# sensorboard.net
KiCad netlist of a schematic drawn in EAGLE
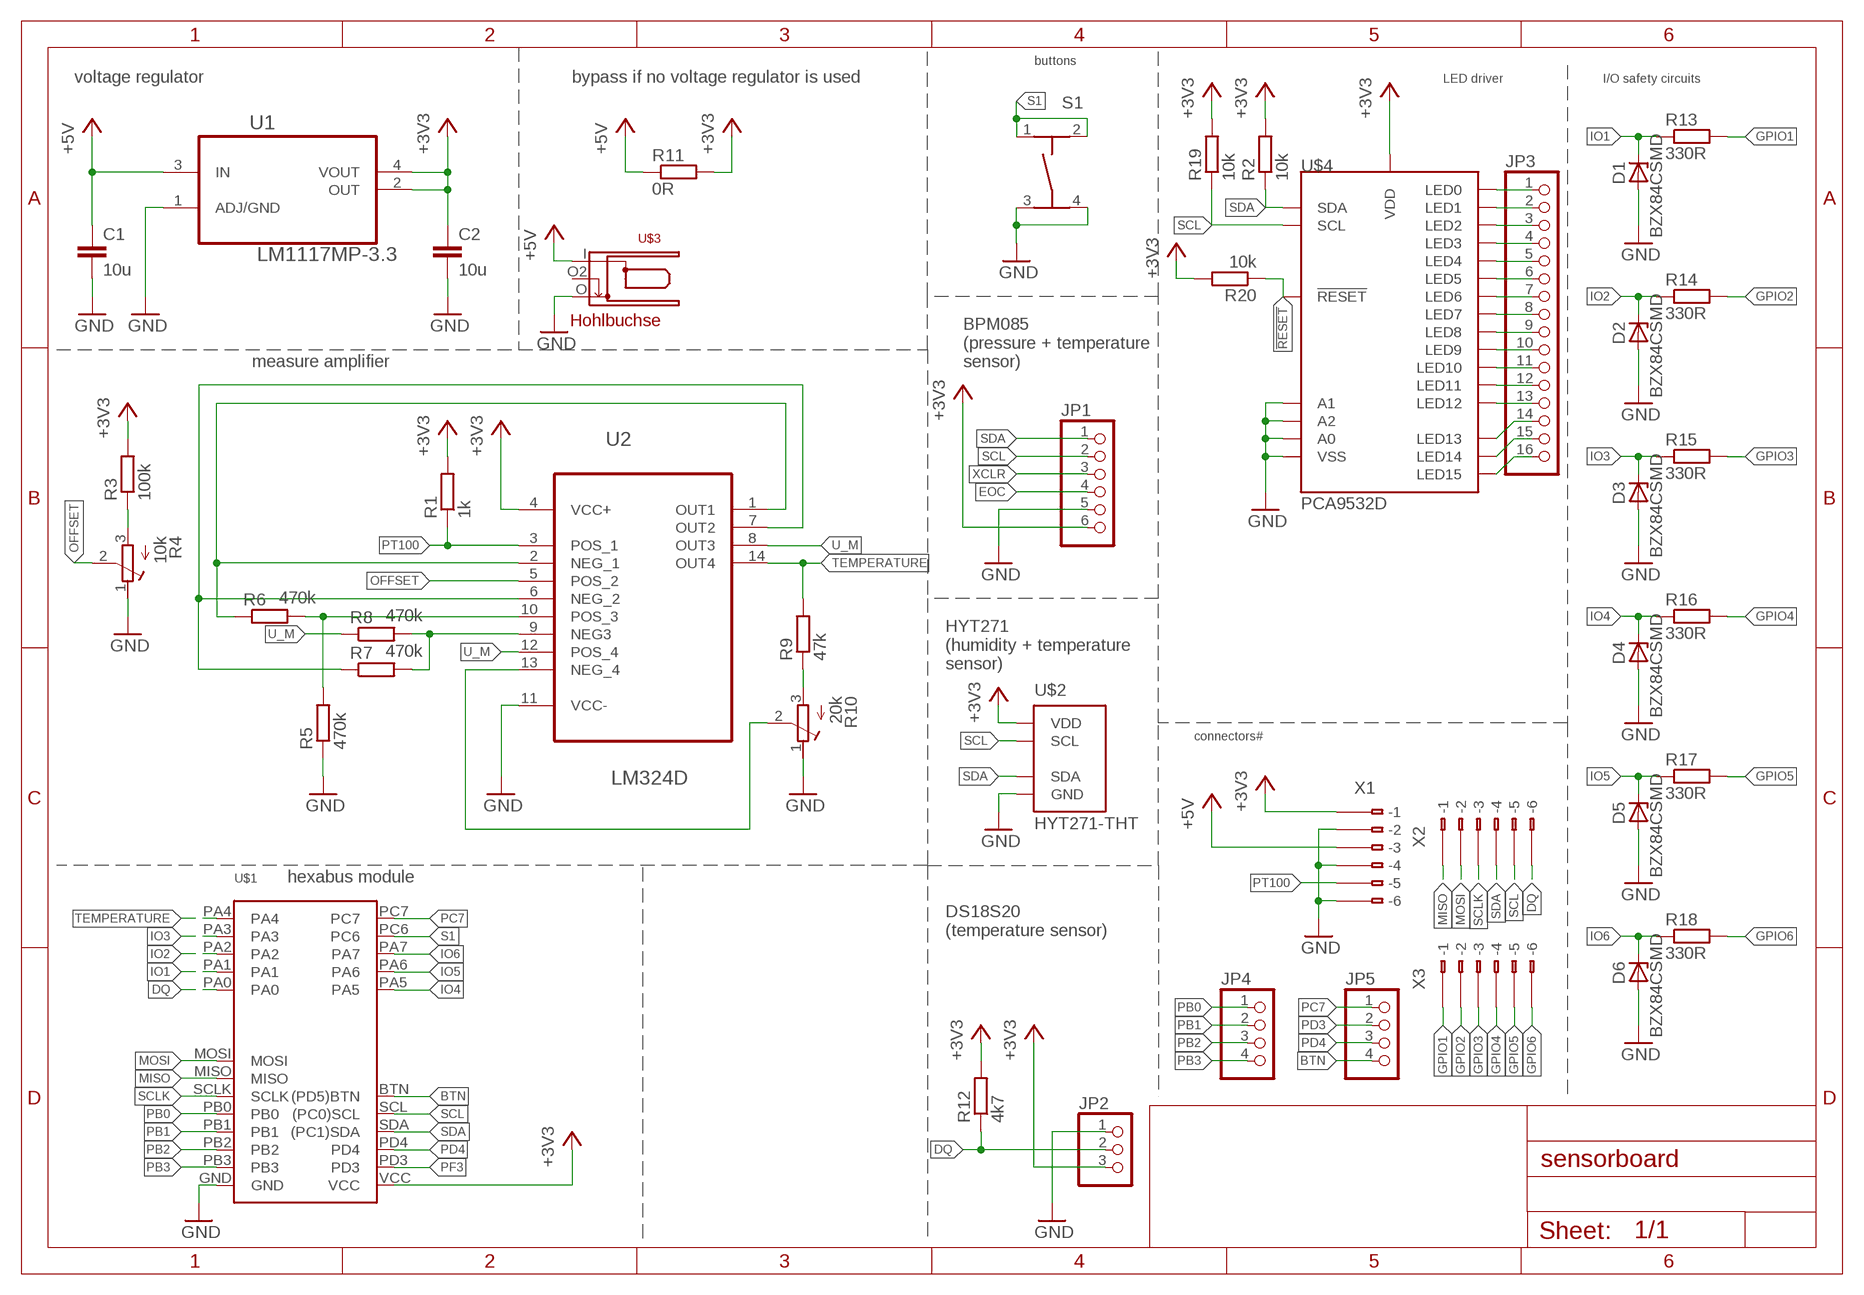
[diagram p0: schematic, sheet 1]

(export (version "E")
  (design (tool "Eeschema 10.0.6"))
  (components
    (comp (ref "C1")
      (value "10u")
      (footprint "eagle-import:C0805")
      (libsource (lib "eagle-import") (part "C-EUC0805"))
    )
    (comp (ref "C2")
      (value "10u")
      (footprint "eagle-import:C0805")
      (libsource (lib "eagle-import") (part "C-EUC0805"))
    )
    (comp (ref "D1")
      (value "BZX84CSMD")
      (footprint "eagle-import:TO236")
      (libsource (lib "eagle-import") (part "BZX84CSMD"))
    )
    (comp (ref "D2")
      (value "BZX84CSMD")
      (footprint "eagle-import:TO236")
      (libsource (lib "eagle-import") (part "BZX84CSMD"))
    )
    (comp (ref "D3")
      (value "BZX84CSMD")
      (footprint "eagle-import:TO236")
      (libsource (lib "eagle-import") (part "BZX84CSMD"))
    )
    (comp (ref "D4")
      (value "BZX84CSMD")
      (footprint "eagle-import:TO236")
      (libsource (lib "eagle-import") (part "BZX84CSMD"))
    )
    (comp (ref "D5")
      (value "BZX84CSMD")
      (footprint "eagle-import:TO236")
      (libsource (lib "eagle-import") (part "BZX84CSMD"))
    )
    (comp (ref "D6")
      (value "BZX84CSMD")
      (footprint "eagle-import:TO236")
      (libsource (lib "eagle-import") (part "BZX84CSMD"))
    )
    (comp (ref "JP1")
      (value "PINHD-1X6")
      (footprint "eagle-import:1X06")
      (libsource (lib "eagle-import") (part "PINHD-1X6"))
    )
    (comp (ref "JP2")
      (value "PINHD-1X3")
      (footprint "eagle-import:1X03")
      (libsource (lib "eagle-import") (part "PINHD-1X3"))
    )
    (comp (ref "JP3")
      (value "PINHD-1X16")
      (footprint "eagle-import:1X16")
      (libsource (lib "eagle-import") (part "PINHD-1X16"))
    )
    (comp (ref "JP4")
      (value "PINHD-1X4")
      (footprint "eagle-import:1X04")
      (libsource (lib "eagle-import") (part "PINHD-1X4"))
    )
    (comp (ref "JP5")
      (value "PINHD-1X4")
      (footprint "eagle-import:1X04")
      (libsource (lib "eagle-import") (part "PINHD-1X4"))
    )
    (comp (ref "R1")
      (value "1k")
      (footprint "eagle-import:R0805")
      (libsource (lib "eagle-import") (part "R-EU_R0805"))
    )
    (comp (ref "R2")
      (value "10k")
      (footprint "eagle-import:R0805")
      (libsource (lib "eagle-import") (part "R-EU_R0805"))
    )
    (comp (ref "R3")
      (value "100k")
      (footprint "eagle-import:R0805")
      (libsource (lib "eagle-import") (part "R-EU_R0805"))
    )
    (comp (ref "R4")
      (value "10k")
      (footprint "eagle-import:RTRIMT93YB")
      (libsource (lib "eagle-import") (part "R-TRIMMT93YB"))
    )
    (comp (ref "R5")
      (value "470k")
      (footprint "eagle-import:R0805")
      (libsource (lib "eagle-import") (part "R-EU_R0805"))
    )
    (comp (ref "R6")
      (value "470k")
      (footprint "eagle-import:R0805")
      (libsource (lib "eagle-import") (part "R-EU_R0805"))
    )
    (comp (ref "R7")
      (value "470k")
      (footprint "eagle-import:R0805")
      (libsource (lib "eagle-import") (part "R-EU_R0805"))
    )
    (comp (ref "R8")
      (value "470k")
      (footprint "eagle-import:R0805")
      (libsource (lib "eagle-import") (part "R-EU_R0805"))
    )
    (comp (ref "R9")
      (value "47k")
      (footprint "eagle-import:R0805")
      (libsource (lib "eagle-import") (part "R-EU_R0805"))
    )
    (comp (ref "R10")
      (value "20k")
      (footprint "eagle-import:RTRIMT93YB")
      (libsource (lib "eagle-import") (part "R-TRIMMT93YB"))
    )
    (comp (ref "R11")
      (value "0R")
      (footprint "eagle-import:R0805")
      (libsource (lib "eagle-import") (part "R-EU_R0805"))
    )
    (comp (ref "R12")
      (value "4k7")
      (footprint "eagle-import:R0805")
      (libsource (lib "eagle-import") (part "R-EU_R0805"))
    )
    (comp (ref "R13")
      (value "330R")
      (footprint "eagle-import:R0805")
      (libsource (lib "eagle-import") (part "R-EU_R0805"))
    )
    (comp (ref "R14")
      (value "330R")
      (footprint "eagle-import:R0805")
      (libsource (lib "eagle-import") (part "R-EU_R0805"))
    )
    (comp (ref "R15")
      (value "330R")
      (footprint "eagle-import:R0805")
      (libsource (lib "eagle-import") (part "R-EU_R0805"))
    )
    (comp (ref "R16")
      (value "330R")
      (footprint "eagle-import:R0805")
      (libsource (lib "eagle-import") (part "R-EU_R0805"))
    )
    (comp (ref "R17")
      (value "330R")
      (footprint "eagle-import:R0805")
      (libsource (lib "eagle-import") (part "R-EU_R0805"))
    )
    (comp (ref "R18")
      (value "330R")
      (footprint "eagle-import:R0805")
      (libsource (lib "eagle-import") (part "R-EU_R0805"))
    )
    (comp (ref "R19")
      (value "10k")
      (footprint "eagle-import:R0805")
      (libsource (lib "eagle-import") (part "R-EU_R0805"))
    )
    (comp (ref "R20")
      (value "10k")
      (footprint "eagle-import:R0805")
      (libsource (lib "eagle-import") (part "R-EU_R0805"))
    )
    (comp (ref "S1")
      (value "TASTER-9314_SMD")
      (footprint "eagle-import:TASTER-9314_SMD")
      (libsource (lib "eagle-import") (part "TASTER-9314_SMD"))
    )
    (comp (ref "U$1")
      (value "HEXABUS")
      (footprint "eagle-import:HEXABUS")
      (libsource (lib "eagle-import") (part "HEXABUS"))
    )
    (comp (ref "U$2")
      (value "HYT271-THT")
      (footprint "eagle-import:HYT271-THT")
      (libsource (lib "eagle-import") (part "HYT271-THT"))
    )
    (comp (ref "U$3")
      (value "HOHLBUCHSE")
      (footprint "eagle-import:HOHLBUCHSE")
      (libsource (lib "eagle-import") (part "HOHLBUCHSE"))
    )
    (comp (ref "U$4")
      (value "PCA9532D")
      (footprint "eagle-import:SO24")
      (libsource (lib "eagle-import") (part "PCA9532D"))
    )
    (comp (ref "U1")
      (value "LM1117MP-3.3")
      (footprint "eagle-import:SOT230P696X180-4N")
      (libsource (lib "eagle-import") (part "LM1117MP-3.3"))
    )
    (comp (ref "U2")
      (value "LM324D")
      (footprint "eagle-import:SOIC127P600X175-14N")
      (libsource (lib "eagle-import") (part "LM324D"))
    )
    (comp (ref "X1")
      (value "233-206")
      (footprint "eagle-import:233-206")
      (libsource (lib "eagle-import") (part "233-206"))
    )
    (comp (ref "X2")
      (value "233-206")
      (footprint "eagle-import:233-206")
      (libsource (lib "eagle-import") (part "233-206"))
    )
    (comp (ref "X3")
      (value "233-206")
      (footprint "eagle-import:233-206")
      (libsource (lib "eagle-import") (part "233-206"))
    )
  )
  (nets
    (net (code "1") (name "+3V3") (class "Default")
      (node (ref "C2") (pin "1") (pinfunction "1_1") (pintype "passive"))
      (node (ref "JP1") (pin "6") (pinfunction "6_6") (pintype "passive"))
      (node (ref "JP2") (pin "3") (pinfunction "3_3") (pintype "passive"))
      (node (ref "R1") (pin "2") (pinfunction "2_2") (pintype "passive"))
      (node (ref "R11") (pin "2") (pinfunction "2_2") (pintype "passive"))
      (node (ref "R12") (pin "2") (pinfunction "2_2") (pintype "passive"))
      (node (ref "R19") (pin "2") (pinfunction "2_2") (pintype "passive"))
      (node (ref "R2") (pin "2") (pinfunction "2_2") (pintype "passive"))
      (node (ref "R20") (pin "2") (pinfunction "2_2") (pintype "passive"))
      (node (ref "R3") (pin "2") (pinfunction "2_2") (pintype "passive"))
      (node (ref "U$1") (pin "VCC") (pinfunction "VCC_VCC") (pintype "bidirectional"))
      (node (ref "U$2") (pin "VDD") (pinfunction "VDD_VDD") (pintype "power_in"))
      (node (ref "U$4") (pin "P$24") (pinfunction "VDD_P$24") (pintype "power_in"))
      (node (ref "U1") (pin "2") (pinfunction "OUT_2") (pintype "output"))
      (node (ref "U1") (pin "4") (pinfunction "VOUT_4") (pintype "output"))
      (node (ref "U2") (pin "4") (pinfunction "VCC+_4") (pintype "power_in"))
      (node (ref "X1") (pin "B1") (pinfunction "B-1_B1") (pintype "passive"))
    )
    (net (code "2") (name "+5V") (class "Default")
      (node (ref "C1") (pin "1") (pinfunction "1_1") (pintype "passive"))
      (node (ref "R11") (pin "1") (pinfunction "1_1") (pintype "passive"))
      (node (ref "U$3") (pin "I") (pinfunction "I_I") (pintype "bidirectional"))
      (node (ref "U1") (pin "3") (pinfunction "IN_3") (pintype "input"))
      (node (ref "X1") (pin "B3") (pinfunction "B-3_B3") (pintype "passive"))
    )
    (net (code "3") (name "/~{RESET}") (class "Default")
      (node (ref "R20") (pin "1") (pinfunction "1_1") (pintype "passive"))
      (node (ref "U$4") (pin "P$21") (pinfunction "~{RESET}_P$21") (pintype "bidirectional"))
    )
    (net (code "4") (name "BTN") (class "Default")
      (node (ref "JP5") (pin "4") (pinfunction "4_4") (pintype "passive"))
      (node (ref "U$1") (pin "BTN") (pinfunction "(PD5)BTN_BTN") (pintype "bidirectional"))
    )
    (net (code "5") (name "DQ") (class "Default")
      (node (ref "JP2") (pin "2") (pinfunction "2_2") (pintype "passive"))
      (node (ref "R12") (pin "1") (pinfunction "1_1") (pintype "passive"))
      (node (ref "U$1") (pin "PA0") (pinfunction "PA0_PA0") (pintype "bidirectional"))
      (node (ref "X2") (pin "B6") (pinfunction "B-6_B6") (pintype "passive"))
    )
    (net (code "6") (name "EOC") (class "Default")
      (node (ref "JP1") (pin "4") (pinfunction "4_4") (pintype "passive"))
    )
    (net (code "7") (name "GND") (class "Default")
      (node (ref "C1") (pin "2") (pinfunction "2_2") (pintype "passive"))
      (node (ref "C2") (pin "2") (pinfunction "2_2") (pintype "passive"))
      (node (ref "D1") (pin "A") (pinfunction "A_A") (pintype "passive"))
      (node (ref "D2") (pin "A") (pinfunction "A_A") (pintype "passive"))
      (node (ref "D3") (pin "A") (pinfunction "A_A") (pintype "passive"))
      (node (ref "D4") (pin "A") (pinfunction "A_A") (pintype "passive"))
      (node (ref "D5") (pin "A") (pinfunction "A_A") (pintype "passive"))
      (node (ref "D6") (pin "A") (pinfunction "A_A") (pintype "passive"))
      (node (ref "JP1") (pin "5") (pinfunction "5_5") (pintype "passive"))
      (node (ref "JP2") (pin "1") (pinfunction "1_1") (pintype "passive"))
      (node (ref "R10") (pin "1") (pinfunction "E_1") (pintype "passive"))
      (node (ref "R4") (pin "1") (pinfunction "E_1") (pintype "passive"))
      (node (ref "R5") (pin "1") (pinfunction "1_1") (pintype "passive"))
      (node (ref "S1") (pin "3") (pinfunction "3_3") (pintype "passive"))
      (node (ref "S1") (pin "4") (pinfunction "4_4") (pintype "passive"))
      (node (ref "U$1") (pin "GND") (pinfunction "GND_GND") (pintype "bidirectional"))
      (node (ref "U$2") (pin "GND") (pinfunction "GND_GND") (pintype "power_in"))
      (node (ref "U$3") (pin "O") (pinfunction "O_O") (pintype "bidirectional"))
      (node (ref "U$4") (pin "P$1") (pinfunction "A0_P$1") (pintype "bidirectional"))
      (node (ref "U$4") (pin "P$12") (pinfunction "VSS_P$12") (pintype "bidirectional"))
      (node (ref "U$4") (pin "P$2") (pinfunction "A1_P$2") (pintype "bidirectional"))
      (node (ref "U$4") (pin "P$3") (pinfunction "A2_P$3") (pintype "bidirectional"))
      (node (ref "U1") (pin "1") (pinfunction "ADJ/GND_1") (pintype "passive"))
      (node (ref "U2") (pin "11") (pinfunction "VCC-_11") (pintype "power_in"))
      (node (ref "X1") (pin "B2") (pinfunction "B-2_B2") (pintype "passive"))
      (node (ref "X1") (pin "B4") (pinfunction "B-4_B4") (pintype "passive"))
      (node (ref "X1") (pin "B6") (pinfunction "B-6_B6") (pintype "passive"))
    )
    (net (code "8") (name "GPIO1") (class "Default")
      (node (ref "R13") (pin "2") (pinfunction "2_2") (pintype "passive"))
      (node (ref "X3") (pin "B1") (pinfunction "B-1_B1") (pintype "passive"))
    )
    (net (code "9") (name "GPIO2") (class "Default")
      (node (ref "R14") (pin "2") (pinfunction "2_2") (pintype "passive"))
      (node (ref "X3") (pin "B2") (pinfunction "B-2_B2") (pintype "passive"))
    )
    (net (code "10") (name "GPIO3") (class "Default")
      (node (ref "R15") (pin "2") (pinfunction "2_2") (pintype "passive"))
      (node (ref "X3") (pin "B3") (pinfunction "B-3_B3") (pintype "passive"))
    )
    (net (code "11") (name "GPIO4") (class "Default")
      (node (ref "R16") (pin "2") (pinfunction "2_2") (pintype "passive"))
      (node (ref "X3") (pin "B4") (pinfunction "B-4_B4") (pintype "passive"))
    )
    (net (code "12") (name "GPIO5") (class "Default")
      (node (ref "R17") (pin "2") (pinfunction "2_2") (pintype "passive"))
      (node (ref "X3") (pin "B5") (pinfunction "B-5_B5") (pintype "passive"))
    )
    (net (code "13") (name "GPIO6") (class "Default")
      (node (ref "R18") (pin "2") (pinfunction "2_2") (pintype "passive"))
      (node (ref "X3") (pin "B6") (pinfunction "B-6_B6") (pintype "passive"))
    )
    (net (code "14") (name "IO1") (class "Default")
      (node (ref "D1") (pin "C") (pinfunction "C_C") (pintype "passive"))
      (node (ref "R13") (pin "1") (pinfunction "1_1") (pintype "passive"))
      (node (ref "U$1") (pin "PA1") (pinfunction "PA1_PA1") (pintype "bidirectional"))
    )
    (net (code "15") (name "IO2") (class "Default")
      (node (ref "D2") (pin "C") (pinfunction "C_C") (pintype "passive"))
      (node (ref "R14") (pin "1") (pinfunction "1_1") (pintype "passive"))
      (node (ref "U$1") (pin "PA2") (pinfunction "PA2_PA2") (pintype "bidirectional"))
    )
    (net (code "16") (name "IO3") (class "Default")
      (node (ref "D3") (pin "C") (pinfunction "C_C") (pintype "passive"))
      (node (ref "R15") (pin "1") (pinfunction "1_1") (pintype "passive"))
      (node (ref "U$1") (pin "PA3") (pinfunction "PA3_PA3") (pintype "bidirectional"))
    )
    (net (code "17") (name "IO4") (class "Default")
      (node (ref "D4") (pin "C") (pinfunction "C_C") (pintype "passive"))
      (node (ref "R16") (pin "1") (pinfunction "1_1") (pintype "passive"))
      (node (ref "U$1") (pin "PA5") (pinfunction "PA5_PA5") (pintype "bidirectional"))
    )
    (net (code "18") (name "IO5") (class "Default")
      (node (ref "D5") (pin "C") (pinfunction "C_C") (pintype "passive"))
      (node (ref "R17") (pin "1") (pinfunction "1_1") (pintype "passive"))
      (node (ref "U$1") (pin "PA6") (pinfunction "PA6_PA6") (pintype "bidirectional"))
    )
    (net (code "19") (name "IO6") (class "Default")
      (node (ref "D6") (pin "C") (pinfunction "C_C") (pintype "passive"))
      (node (ref "R18") (pin "1") (pinfunction "1_1") (pintype "passive"))
      (node (ref "U$1") (pin "PA7") (pinfunction "PA7_PA7") (pintype "bidirectional"))
    )
    (net (code "20") (name "MISO") (class "Default")
      (node (ref "U$1") (pin "MISO") (pinfunction "MISO_MISO") (pintype "bidirectional"))
      (node (ref "X2") (pin "B1") (pinfunction "B-1_B1") (pintype "passive"))
    )
    (net (code "21") (name "MOSI") (class "Default")
      (node (ref "U$1") (pin "MOSI") (pinfunction "MOSI_MOSI") (pintype "bidirectional"))
      (node (ref "X2") (pin "B2") (pinfunction "B-2_B2") (pintype "passive"))
    )
    (net (code "22") (name "Net-(R4-A)") (class "Default")
      (node (ref "R3") (pin "1") (pinfunction "1_1") (pintype "passive"))
      (node (ref "R4") (pin "3") (pinfunction "A_3") (pintype "passive"))
    )
    (net (code "23") (name "Net-(R10-A)") (class "Default")
      (node (ref "R10") (pin "3") (pinfunction "A_3") (pintype "passive"))
      (node (ref "R9") (pin "1") (pinfunction "1_1") (pintype "passive"))
    )
    (net (code "24") (name "Net-(R10-S)") (class "Default")
      (node (ref "R10") (pin "2") (pinfunction "S_2") (pintype "passive"))
      (node (ref "U2") (pin "13") (pinfunction "NEG_4_13") (pintype "input"))
    )
    (net (code "25") (name "Net-(U$4-LED0)") (class "Default")
      (node (ref "JP3") (pin "1") (pinfunction "1_1") (pintype "passive"))
      (node (ref "U$4") (pin "P$4") (pinfunction "LED0_P$4") (pintype "bidirectional"))
    )
    (net (code "26") (name "Net-(U$4-LED1)") (class "Default")
      (node (ref "JP3") (pin "2") (pinfunction "2_2") (pintype "passive"))
      (node (ref "U$4") (pin "P$5") (pinfunction "LED1_P$5") (pintype "bidirectional"))
    )
    (net (code "27") (name "Net-(U$4-LED2)") (class "Default")
      (node (ref "JP3") (pin "3") (pinfunction "3_3") (pintype "passive"))
      (node (ref "U$4") (pin "P$6") (pinfunction "LED2_P$6") (pintype "bidirectional"))
    )
    (net (code "28") (name "Net-(U$4-LED3)") (class "Default")
      (node (ref "JP3") (pin "4") (pinfunction "4_4") (pintype "passive"))
      (node (ref "U$4") (pin "P$7") (pinfunction "LED3_P$7") (pintype "bidirectional"))
    )
    (net (code "29") (name "Net-(U$4-LED4)") (class "Default")
      (node (ref "JP3") (pin "5") (pinfunction "5_5") (pintype "passive"))
      (node (ref "U$4") (pin "P$8") (pinfunction "LED4_P$8") (pintype "bidirectional"))
    )
    (net (code "30") (name "Net-(U$4-LED5)") (class "Default")
      (node (ref "JP3") (pin "6") (pinfunction "6_6") (pintype "passive"))
      (node (ref "U$4") (pin "P$9") (pinfunction "LED5_P$9") (pintype "bidirectional"))
    )
    (net (code "31") (name "Net-(U$4-LED6)") (class "Default")
      (node (ref "JP3") (pin "7") (pinfunction "7_7") (pintype "passive"))
      (node (ref "U$4") (pin "P$10") (pinfunction "LED6_P$10") (pintype "bidirectional"))
    )
    (net (code "32") (name "Net-(U$4-LED7)") (class "Default")
      (node (ref "JP3") (pin "8") (pinfunction "8_8") (pintype "passive"))
      (node (ref "U$4") (pin "P$11") (pinfunction "LED7_P$11") (pintype "bidirectional"))
    )
    (net (code "33") (name "Net-(U$4-LED8)") (class "Default")
      (node (ref "JP3") (pin "9") (pinfunction "9_9") (pintype "passive"))
      (node (ref "U$4") (pin "P$13") (pinfunction "LED8_P$13") (pintype "bidirectional"))
    )
    (net (code "34") (name "Net-(U$4-LED9)") (class "Default")
      (node (ref "JP3") (pin "10") (pinfunction "10_10") (pintype "passive"))
      (node (ref "U$4") (pin "P$14") (pinfunction "LED9_P$14") (pintype "bidirectional"))
    )
    (net (code "35") (name "Net-(U$4-LED10)") (class "Default")
      (node (ref "JP3") (pin "11") (pinfunction "11_11") (pintype "passive"))
      (node (ref "U$4") (pin "P$15") (pinfunction "LED10_P$15") (pintype "bidirectional"))
    )
    (net (code "36") (name "Net-(U$4-LED11)") (class "Default")
      (node (ref "JP3") (pin "12") (pinfunction "12_12") (pintype "passive"))
      (node (ref "U$4") (pin "P$16") (pinfunction "LED11_P$16") (pintype "bidirectional"))
    )
    (net (code "37") (name "Net-(U$4-LED12)") (class "Default")
      (node (ref "JP3") (pin "13") (pinfunction "13_13") (pintype "passive"))
      (node (ref "U$4") (pin "P$17") (pinfunction "LED12_P$17") (pintype "bidirectional"))
    )
    (net (code "38") (name "Net-(U$4-LED13)") (class "Default")
      (node (ref "JP3") (pin "14") (pinfunction "14_14") (pintype "passive"))
      (node (ref "U$4") (pin "P$18") (pinfunction "LED13_P$18") (pintype "bidirectional"))
    )
    (net (code "39") (name "Net-(U$4-LED14)") (class "Default")
      (node (ref "JP3") (pin "15") (pinfunction "15_15") (pintype "passive"))
      (node (ref "U$4") (pin "P$19") (pinfunction "LED14_P$19") (pintype "bidirectional"))
    )
    (net (code "40") (name "Net-(U$4-LED15)") (class "Default")
      (node (ref "JP3") (pin "16") (pinfunction "16_16") (pintype "passive"))
      (node (ref "U$4") (pin "P$20") (pinfunction "LED15_P$20") (pintype "bidirectional"))
    )
    (net (code "41") (name "Net-(U2-NEG3)") (class "Default")
      (node (ref "R7") (pin "2") (pinfunction "2_2") (pintype "passive"))
      (node (ref "R8") (pin "2") (pinfunction "2_2") (pintype "passive"))
      (node (ref "U2") (pin "9") (pinfunction "NEG3_9") (pintype "input"))
    )
    (net (code "42") (name "Net-(U2-NEG_1)") (class "Default")
      (node (ref "R6") (pin "1") (pinfunction "1_1") (pintype "passive"))
      (node (ref "U2") (pin "1") (pinfunction "OUT1_1") (pintype "output"))
      (node (ref "U2") (pin "2") (pinfunction "NEG_1_2") (pintype "input"))
    )
    (net (code "43") (name "Net-(U2-NEG_2)") (class "Default")
      (node (ref "R7") (pin "1") (pinfunction "1_1") (pintype "passive"))
      (node (ref "U2") (pin "6") (pinfunction "NEG_2_6") (pintype "input"))
      (node (ref "U2") (pin "7") (pinfunction "OUT2_7") (pintype "output"))
    )
    (net (code "44") (name "Net-(U2-POS_3)") (class "Default")
      (node (ref "R5") (pin "2") (pinfunction "2_2") (pintype "passive"))
      (node (ref "R6") (pin "2") (pinfunction "2_2") (pintype "passive"))
      (node (ref "U2") (pin "10") (pinfunction "POS_3_10") (pintype "input"))
    )
    (net (code "45") (name "OFFSET") (class "Default")
      (node (ref "R4") (pin "2") (pinfunction "S_2") (pintype "passive"))
      (node (ref "U2") (pin "5") (pinfunction "POS_2_5") (pintype "input"))
    )
    (net (code "46") (name "PB0") (class "Default")
      (node (ref "JP4") (pin "1") (pinfunction "1_1") (pintype "passive"))
      (node (ref "U$1") (pin "PB0") (pinfunction "PB0_PB0") (pintype "bidirectional"))
    )
    (net (code "47") (name "PB1") (class "Default")
      (node (ref "JP4") (pin "2") (pinfunction "2_2") (pintype "passive"))
      (node (ref "U$1") (pin "PB1") (pinfunction "PB1_PB1") (pintype "bidirectional"))
    )
    (net (code "48") (name "PB2") (class "Default")
      (node (ref "JP4") (pin "3") (pinfunction "3_3") (pintype "passive"))
      (node (ref "U$1") (pin "PB2") (pinfunction "PB2_PB2") (pintype "bidirectional"))
    )
    (net (code "49") (name "PB3") (class "Default")
      (node (ref "JP4") (pin "4") (pinfunction "4_4") (pintype "passive"))
      (node (ref "U$1") (pin "PB3") (pinfunction "PB3_PB3") (pintype "bidirectional"))
    )
    (net (code "50") (name "PC7") (class "Default")
      (node (ref "JP5") (pin "1") (pinfunction "1_1") (pintype "passive"))
      (node (ref "U$1") (pin "PC7") (pinfunction "PC7_PC7") (pintype "bidirectional"))
    )
    (net (code "51") (name "PD3") (class "Default")
      (node (ref "JP5") (pin "2") (pinfunction "2_2") (pintype "passive"))
    )
    (net (code "52") (name "PD4") (class "Default")
      (node (ref "JP5") (pin "3") (pinfunction "3_3") (pintype "passive"))
      (node (ref "U$1") (pin "PD4") (pinfunction "PD4_PD4") (pintype "bidirectional"))
    )
    (net (code "53") (name "PF3") (class "Default")
      (node (ref "U$1") (pin "PD3") (pinfunction "PD3_PD3") (pintype "bidirectional"))
    )
    (net (code "54") (name "PT100") (class "Default")
      (node (ref "R1") (pin "1") (pinfunction "1_1") (pintype "passive"))
      (node (ref "U2") (pin "3") (pinfunction "POS_1_3") (pintype "input"))
      (node (ref "X1") (pin "B5") (pinfunction "B-5_B5") (pintype "passive"))
    )
    (net (code "55") (name "S1") (class "Default")
      (node (ref "S1") (pin "1") (pinfunction "1_1") (pintype "passive"))
      (node (ref "S1") (pin "2") (pinfunction "2_2") (pintype "passive"))
      (node (ref "U$1") (pin "PC6") (pinfunction "PC6_PC6") (pintype "bidirectional"))
    )
    (net (code "56") (name "SCL") (class "Default")
      (node (ref "JP1") (pin "2") (pinfunction "2_2") (pintype "passive"))
      (node (ref "R19") (pin "1") (pinfunction "1_1") (pintype "passive"))
      (node (ref "U$1") (pin "SCL") (pinfunction "(PC0)SCL_SCL") (pintype "bidirectional"))
      (node (ref "U$2") (pin "SCL") (pinfunction "SCL_SCL") (pintype "bidirectional"))
      (node (ref "U$4") (pin "P$22") (pinfunction "SCL_P$22") (pintype "bidirectional"))
      (node (ref "X2") (pin "B5") (pinfunction "B-5_B5") (pintype "passive"))
    )
    (net (code "57") (name "SCLK") (class "Default")
      (node (ref "U$1") (pin "SCLK") (pinfunction "SCLK_SCLK") (pintype "bidirectional"))
      (node (ref "X2") (pin "B3") (pinfunction "B-3_B3") (pintype "passive"))
    )
    (net (code "58") (name "SDA") (class "Default")
      (node (ref "JP1") (pin "1") (pinfunction "1_1") (pintype "passive"))
      (node (ref "R2") (pin "1") (pinfunction "1_1") (pintype "passive"))
      (node (ref "U$1") (pin "SDA") (pinfunction "(PC1)SDA_SDA") (pintype "bidirectional"))
      (node (ref "U$2") (pin "SDA") (pinfunction "SDA_SDA") (pintype "bidirectional"))
      (node (ref "U$4") (pin "P$23") (pinfunction "SDA_P$23") (pintype "bidirectional"))
      (node (ref "X2") (pin "B4") (pinfunction "B-4_B4") (pintype "passive"))
    )
    (net (code "59") (name "TEMPERATURE") (class "Default")
      (node (ref "R9") (pin "2") (pinfunction "2_2") (pintype "passive"))
      (node (ref "U$1") (pin "PA4") (pinfunction "PA4_PA4") (pintype "bidirectional"))
      (node (ref "U2") (pin "14") (pinfunction "OUT4_14") (pintype "output"))
    )
    (net (code "60") (name "U_M") (class "Default")
      (node (ref "R8") (pin "1") (pinfunction "1_1") (pintype "passive"))
      (node (ref "U2") (pin "12") (pinfunction "POS_4_12") (pintype "input"))
      (node (ref "U2") (pin "8") (pinfunction "OUT3_8") (pintype "output"))
    )
    (net (code "61") (name "XCLR") (class "Default")
      (node (ref "JP1") (pin "3") (pinfunction "3_3") (pintype "passive"))
    )
    (net (code "62") (name "unconnected-(U$3-PadO2)") (class "Default")
      (node (ref "U$3") (pin "O2") (pinfunction "O2_O2") (pintype "bidirectional"))
    )
    (net (code "63") (name "unconnected-(X1--1-PadA1)") (class "Default")
      (node (ref "X1") (pin "A1") (pinfunction "-1_A1") (pintype "passive"))
    )
    (net (code "64") (name "unconnected-(X1--2-PadA2)") (class "Default")
      (node (ref "X1") (pin "A2") (pinfunction "-2_A2") (pintype "passive"))
    )
    (net (code "65") (name "unconnected-(X1--3-PadA3)") (class "Default")
      (node (ref "X1") (pin "A3") (pinfunction "-3_A3") (pintype "passive"))
    )
    (net (code "66") (name "unconnected-(X1--4-PadA4)") (class "Default")
      (node (ref "X1") (pin "A4") (pinfunction "-4_A4") (pintype "passive"))
    )
    (net (code "67") (name "unconnected-(X1--5-PadA5)") (class "Default")
      (node (ref "X1") (pin "A5") (pinfunction "-5_A5") (pintype "passive"))
    )
    (net (code "68") (name "unconnected-(X1--6-PadA6)") (class "Default")
      (node (ref "X1") (pin "A6") (pinfunction "-6_A6") (pintype "passive"))
    )
    (net (code "69") (name "unconnected-(X2--1-PadA1)") (class "Default")
      (node (ref "X2") (pin "A1") (pinfunction "-1_A1") (pintype "passive"))
    )
    (net (code "70") (name "unconnected-(X2--2-PadA2)") (class "Default")
      (node (ref "X2") (pin "A2") (pinfunction "-2_A2") (pintype "passive"))
    )
    (net (code "71") (name "unconnected-(X2--3-PadA3)") (class "Default")
      (node (ref "X2") (pin "A3") (pinfunction "-3_A3") (pintype "passive"))
    )
    (net (code "72") (name "unconnected-(X2--4-PadA4)") (class "Default")
      (node (ref "X2") (pin "A4") (pinfunction "-4_A4") (pintype "passive"))
    )
    (net (code "73") (name "unconnected-(X2--5-PadA5)") (class "Default")
      (node (ref "X2") (pin "A5") (pinfunction "-5_A5") (pintype "passive"))
    )
    (net (code "74") (name "unconnected-(X2--6-PadA6)") (class "Default")
      (node (ref "X2") (pin "A6") (pinfunction "-6_A6") (pintype "passive"))
    )
    (net (code "75") (name "unconnected-(X3--1-PadA1)") (class "Default")
      (node (ref "X3") (pin "A1") (pinfunction "-1_A1") (pintype "passive"))
    )
    (net (code "76") (name "unconnected-(X3--2-PadA2)") (class "Default")
      (node (ref "X3") (pin "A2") (pinfunction "-2_A2") (pintype "passive"))
    )
    (net (code "77") (name "unconnected-(X3--3-PadA3)") (class "Default")
      (node (ref "X3") (pin "A3") (pinfunction "-3_A3") (pintype "passive"))
    )
    (net (code "78") (name "unconnected-(X3--4-PadA4)") (class "Default")
      (node (ref "X3") (pin "A4") (pinfunction "-4_A4") (pintype "passive"))
    )
    (net (code "79") (name "unconnected-(X3--5-PadA5)") (class "Default")
      (node (ref "X3") (pin "A5") (pinfunction "-5_A5") (pintype "passive"))
    )
    (net (code "80") (name "unconnected-(X3--6-PadA6)") (class "Default")
      (node (ref "X3") (pin "A6") (pinfunction "-6_A6") (pintype "passive"))
    )
  )
)
